# User_Interface.net
KiCad netlist of a schematic drawn in Altium Designer
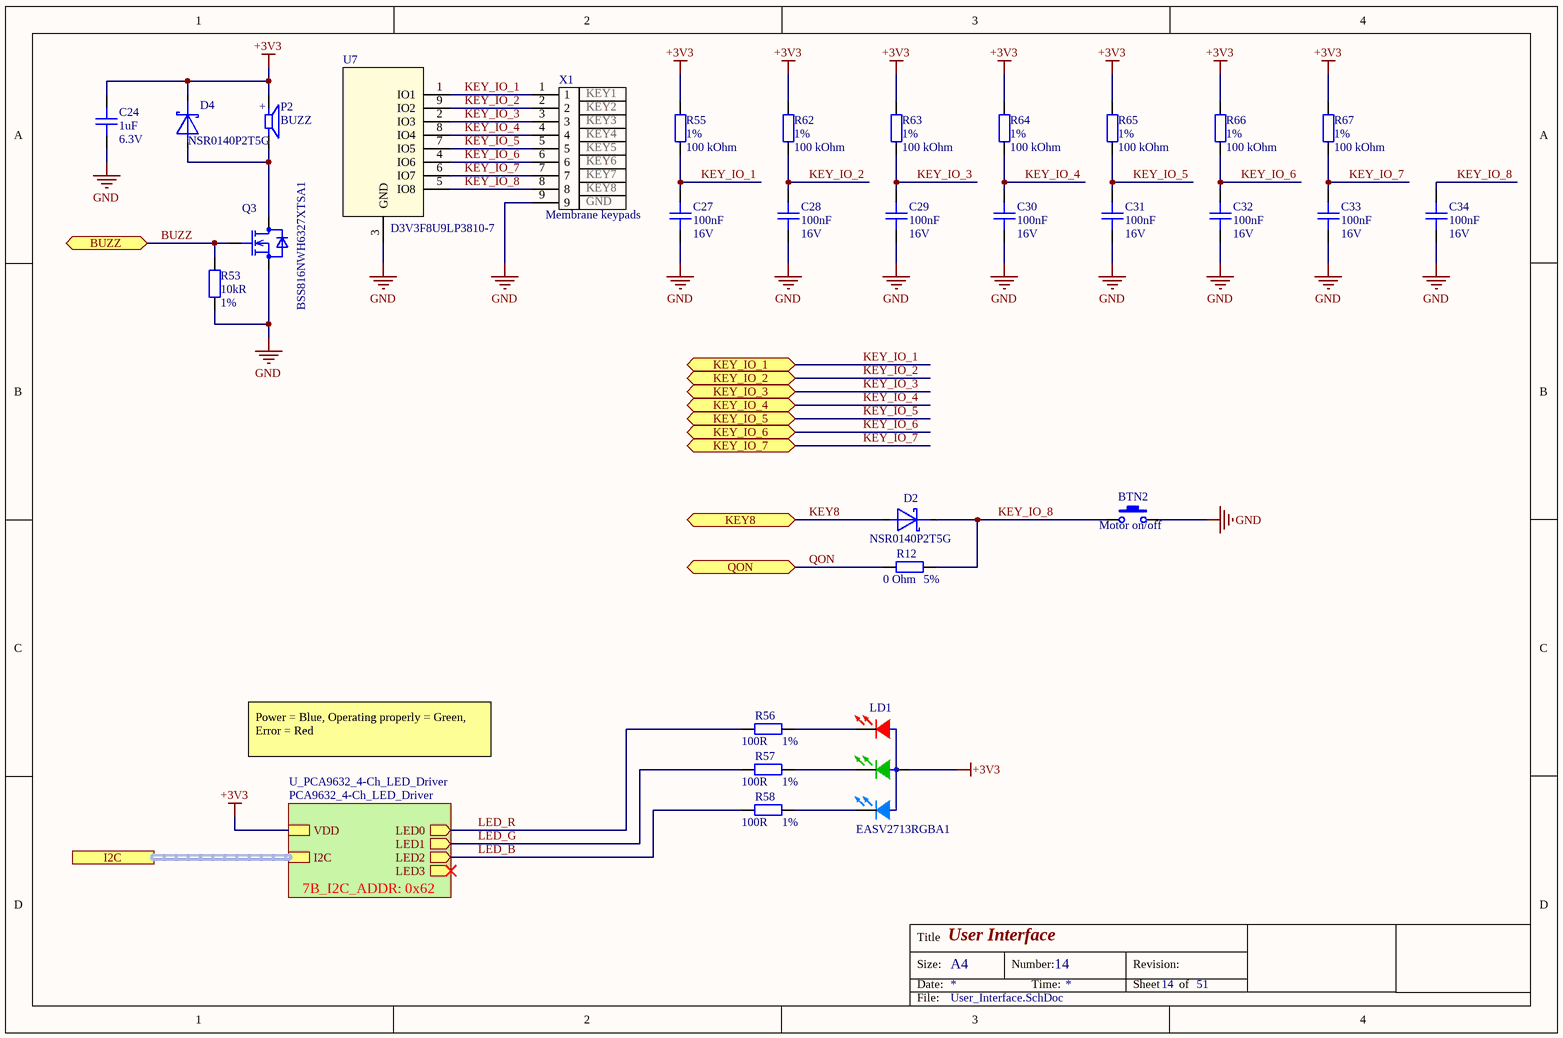
[diagram p0: User_Interface.SchDoc]

(export (version "E")
  (design (tool "Eeschema 10.0.6"))
  (components
    (comp (ref "BTN2")
      (value "Motor on/off")
      (footprint "SWITCH KMS231GLFS")
      (description "SWITCH TACTILE SPST-NO 0.05A 50V")
      (fields (field (name "MANUFACTURER") "C&K") (field (name "MANUFACTURER PART NUMBER") "KMS231GLFS"))
      (libsource (lib "Control_Board_Model") (part "SWITCH TACTILE SPST-NO 0.05A 50V"))
    )
    (comp (ref "C24")
      (value "CAP CER 1UF 6.3V X5R 0402")
      (footprint "C0402")
      (description "1µF ±10% 6.3V Ceramic Capacitor X5R 0402 (1005 Metric)")
      (fields
        (field (name "MANUFACTURER") "Yageo")
        (field (name "MANUFACTURER PART NUMBER") "CC0402KRX5R5BB105")
        (field (name "CAPACITANCE") "1uF")
        (field (name "VOLTAGE RATING") "6.3V")
      )
      (libsource (lib "capacitors_smd") (part "CAP CER 1UF 6.3V X5R 0402"))
    )
    (comp (ref "C27")
      (value "CAP CER 0.1UF 16V X7R 0402")
      (footprint "C0402")
      (description "0.1µF ±10% 16V Ceramic Capacitor X7R 0402 (1005 Metric)")
      (fields
        (field (name "MANUFACTURER PART NUMBER") "CC0402KRX7R7BB104")
        (field (name "MANUFACTURER") "Yageo")
        (field (name "CAPACITANCE") "100nF")
        (field (name "VOLTAGE") "16V")
      )
      (libsource (lib "capacitors_smd") (part "CAP CER 0.1UF 16V X7R 0402"))
    )
    (comp (ref "C28")
      (value "CAP CER 0.1UF 16V X7R 0402")
      (footprint "C0402")
      (description "0.1µF ±10% 16V Ceramic Capacitor X7R 0402 (1005 Metric)")
      (fields
        (field (name "MANUFACTURER PART NUMBER") "CC0402KRX7R7BB104")
        (field (name "MANUFACTURER") "Yageo")
        (field (name "CAPACITANCE") "100nF")
        (field (name "VOLTAGE") "16V")
      )
      (libsource (lib "capacitors_smd") (part "CAP CER 0.1UF 16V X7R 0402"))
    )
    (comp (ref "C29")
      (value "CAP CER 0.1UF 16V X7R 0402")
      (footprint "C0402")
      (description "0.1µF ±10% 16V Ceramic Capacitor X7R 0402 (1005 Metric)")
      (fields
        (field (name "MANUFACTURER PART NUMBER") "CC0402KRX7R7BB104")
        (field (name "MANUFACTURER") "Yageo")
        (field (name "CAPACITANCE") "100nF")
        (field (name "VOLTAGE") "16V")
      )
      (libsource (lib "capacitors_smd") (part "CAP CER 0.1UF 16V X7R 0402"))
    )
    (comp (ref "C30")
      (value "CAP CER 0.1UF 16V X7R 0402")
      (footprint "C0402")
      (description "0.1µF ±10% 16V Ceramic Capacitor X7R 0402 (1005 Metric)")
      (fields
        (field (name "MANUFACTURER PART NUMBER") "CC0402KRX7R7BB104")
        (field (name "MANUFACTURER") "Yageo")
        (field (name "CAPACITANCE") "100nF")
        (field (name "VOLTAGE") "16V")
      )
      (libsource (lib "capacitors_smd") (part "CAP CER 0.1UF 16V X7R 0402"))
    )
    (comp (ref "C31")
      (value "CAP CER 0.1UF 16V X7R 0402")
      (footprint "C0402")
      (description "0.1µF ±10% 16V Ceramic Capacitor X7R 0402 (1005 Metric)")
      (fields
        (field (name "MANUFACTURER PART NUMBER") "CC0402KRX7R7BB104")
        (field (name "MANUFACTURER") "Yageo")
        (field (name "CAPACITANCE") "100nF")
        (field (name "VOLTAGE") "16V")
      )
      (libsource (lib "capacitors_smd") (part "CAP CER 0.1UF 16V X7R 0402"))
    )
    (comp (ref "C32")
      (value "CAP CER 0.1UF 16V X7R 0402")
      (footprint "C0402")
      (description "0.1µF ±10% 16V Ceramic Capacitor X7R 0402 (1005 Metric)")
      (fields
        (field (name "MANUFACTURER PART NUMBER") "CC0402KRX7R7BB104")
        (field (name "MANUFACTURER") "Yageo")
        (field (name "CAPACITANCE") "100nF")
        (field (name "VOLTAGE") "16V")
      )
      (libsource (lib "capacitors_smd") (part "CAP CER 0.1UF 16V X7R 0402"))
    )
    (comp (ref "C33")
      (value "CAP CER 0.1UF 16V X7R 0402")
      (footprint "C0402")
      (description "0.1µF ±10% 16V Ceramic Capacitor X7R 0402 (1005 Metric)")
      (fields
        (field (name "MANUFACTURER PART NUMBER") "CC0402KRX7R7BB104")
        (field (name "MANUFACTURER") "Yageo")
        (field (name "CAPACITANCE") "100nF")
        (field (name "VOLTAGE") "16V")
      )
      (libsource (lib "capacitors_smd") (part "CAP CER 0.1UF 16V X7R 0402"))
    )
    (comp (ref "C34")
      (value "CAP CER 0.1UF 16V X7R 0402")
      (footprint "C0402")
      (description "0.1µF ±10% 16V Ceramic Capacitor X7R 0402 (1005 Metric)")
      (fields
        (field (name "MANUFACTURER PART NUMBER") "CC0402KRX7R7BB104")
        (field (name "MANUFACTURER") "Yageo")
        (field (name "CAPACITANCE") "100nF")
        (field (name "VOLTAGE") "16V")
      )
      (libsource (lib "capacitors_smd") (part "CAP CER 0.1UF 16V X7R 0402"))
    )
    (comp (ref "D2")
      (value "NSR0140P2T5G")
      (footprint "SODFL100X40-2N")
      (description "Diode Schottky 30V 70mA (DC) Surface Mount SOD-923")
      (fields (field (name "MANUFACTURER") "ON Semiconductor"))
      (libsource (lib "Control_Board_Model") (part "DIODE SCHOTTKY 30V 70MA SOD923"))
    )
    (comp (ref "D4")
      (value "NSR0140P2T5G")
      (footprint "SODFL100X40-2N")
      (description "Diode Schottky 30V 70mA (DC) Surface Mount SOD-923")
      (fields (field (name "MANUFACTURER") "ON Semiconductor"))
      (libsource (lib "diodes_schottky") (part "DIODE SCHOTTKY 30V 70MA SOD923"))
    )
    (comp (ref "LD1")
      (value "EASV2713RGBA1")
      (footprint "LED_EASV2713RGBA1")
      (fields (field (name "MANUFACTURER") "Everlight Electronics Co Ltd"))
      (libsource (lib "Control_Board_Model") (part "LED RGB PCB SIDE VIEW SMD"))
    )
    (comp (ref "P2")
      (value "BUZZ")
      (footprint "SMT-0440-S-R_PUI")
      (description "Buzzers Transducer, Externally Driven 90mA 4kHz 70dB @ 3V, 10cm Surface Mount Solder Pads")
      (fields
        (field (name "MANUFACTURER") "Projects Unlimited")
        (field (name "MANUFACTURER PART NUMBER") "SMT-0440-S-R")
      )
      (libsource (lib "BLDC_Motor_Driver") (part "AUDIO MAGNETIC XDCR 2-4V SMD"))
    )
    (comp (ref "Q3")
      (value "BSS816NWH6327XTSA1")
      (footprint "SOT-323")
      (description "N-Channel 20V 1.4A (Ta) 500mW (Ta) Surface Mount PG-SOT323-3")
      (fields (field (name "MANUFACTURER") "Infineon"))
      (libsource (lib "mosfets") (part "MOSFET BSS816NWH6327XTSA1 N-CH 20V 1.4A SOT323"))
    )
    (comp (ref "R12")
      (value "RES SMD 0 OHM JUMPER 1/16W 0402")
      (footprint "R0402")
      (description "0 Ohms Jumper 0.063W, 1/16W Chip Resistor 0402 (1005 Metric) Moisture Resistant Thick Film")
      (fields
        (field (name "MANUFACTURER") "Yageo")
        (field (name "MANUFACTURER PART NUMBER") "RC0402JR-070RL")
        (field (name "TOLERANCE") "5%")
        (field (name "RESISTANCE") "0 Ohm")
      )
      (libsource (lib "resistors_smd") (part "RES SMD 0 OHM JUMPER 1/16W 0402"))
    )
    (comp (ref "R53")
      (value "RES SMD 10K OHM 1% 1/16W 0402")
      (footprint "R0402")
      (description "10 kOhms ±1% 0.063W, 1/16W Chip Resistor 0402 (1005 Metric) Moisture Resistant Thick Film")
      (fields
        (field (name "MANUFACTURER PART NUMBER") "RC0402FR-0710KP")
        (field (name "MANUFACTURER") "Yageo")
        (field (name "RESISTANCE") "10kR")
        (field (name "TOLERANCE") "1%")
      )
      (libsource (lib "resistors_smd") (part "RES SMD 10K OHM 1% 1/16W 0402"))
    )
    (comp (ref "R55")
      (value "RES SMD 100K OHM 1% 1/16W 0402")
      (footprint "R0402")
      (description "100 kOhms ±1% 0.063W, 1/16W Chip Resistor 0402 (1005 Metric) Moisture Resistant Thick Film")
      (fields
        (field (name "MANUFACTURER") "Yageo")
        (field (name "MANUFACTURER PART NUMBER") "RC0402FR-07100KL")
        (field (name "TOLERANCE") "1%")
        (field (name "RESISTANCE") "100 kOhm")
      )
      (libsource (lib "Control_Board_Model") (part "RES SMD 100K OHM 1% 1/16W 0402"))
    )
    (comp (ref "R56")
      (value "RES SMD 100 OHM 1% 1/16W 0402")
      (footprint "R0402")
      (description "100 Ohms ±1% 0.063W, 1/16W Chip Resistor 0402 (1005 Metric) Moisture Resistant Thick Film")
      (fields
        (field (name "MANUFACTURER") "Yageo")
        (field (name "MANUFACTURER PART NUMBER") "RC0402FR-07100RL")
        (field (name "TOLERANCE") "1%")
        (field (name "RESISTANCE") "100R")
      )
      (libsource (lib "Control_Board_Model") (part "RES SMD 100 OHM 1% 1/16W 0402"))
    )
    (comp (ref "R57")
      (value "RES SMD 100 OHM 1% 1/16W 0402")
      (footprint "R0402")
      (description "100 Ohms ±1% 0.063W, 1/16W Chip Resistor 0402 (1005 Metric) Moisture Resistant Thick Film")
      (fields
        (field (name "MANUFACTURER") "Yageo")
        (field (name "MANUFACTURER PART NUMBER") "RC0402FR-07100RL")
        (field (name "TOLERANCE") "1%")
        (field (name "RESISTANCE") "100R")
      )
      (libsource (lib "Control_Board_Model") (part "RES SMD 100 OHM 1% 1/16W 0402"))
    )
    (comp (ref "R58")
      (value "RES SMD 100 OHM 1% 1/16W 0402")
      (footprint "R0402")
      (description "100 Ohms ±1% 0.063W, 1/16W Chip Resistor 0402 (1005 Metric) Moisture Resistant Thick Film")
      (fields
        (field (name "MANUFACTURER") "Yageo")
        (field (name "MANUFACTURER PART NUMBER") "RC0402FR-07100RL")
        (field (name "TOLERANCE") "1%")
        (field (name "RESISTANCE") "100R")
      )
      (libsource (lib "Control_Board_Model") (part "RES SMD 100 OHM 1% 1/16W 0402"))
    )
    (comp (ref "R62")
      (value "RES SMD 100K OHM 1% 1/16W 0402")
      (footprint "R0402")
      (description "100 kOhms ±1% 0.063W, 1/16W Chip Resistor 0402 (1005 Metric) Moisture Resistant Thick Film")
      (fields
        (field (name "MANUFACTURER") "Yageo")
        (field (name "MANUFACTURER PART NUMBER") "RC0402FR-07100KL")
        (field (name "TOLERANCE") "1%")
        (field (name "RESISTANCE") "100 kOhm")
      )
      (libsource (lib "Control_Board_Model") (part "RES SMD 100K OHM 1% 1/16W 0402"))
    )
    (comp (ref "R63")
      (value "RES SMD 100K OHM 1% 1/16W 0402")
      (footprint "R0402")
      (description "100 kOhms ±1% 0.063W, 1/16W Chip Resistor 0402 (1005 Metric) Moisture Resistant Thick Film")
      (fields
        (field (name "MANUFACTURER") "Yageo")
        (field (name "MANUFACTURER PART NUMBER") "RC0402FR-07100KL")
        (field (name "TOLERANCE") "1%")
        (field (name "RESISTANCE") "100 kOhm")
      )
      (libsource (lib "Control_Board_Model") (part "RES SMD 100K OHM 1% 1/16W 0402"))
    )
    (comp (ref "R64")
      (value "RES SMD 100K OHM 1% 1/16W 0402")
      (footprint "R0402")
      (description "100 kOhms ±1% 0.063W, 1/16W Chip Resistor 0402 (1005 Metric) Moisture Resistant Thick Film")
      (fields
        (field (name "MANUFACTURER") "Yageo")
        (field (name "MANUFACTURER PART NUMBER") "RC0402FR-07100KL")
        (field (name "TOLERANCE") "1%")
        (field (name "RESISTANCE") "100 kOhm")
      )
      (libsource (lib "Control_Board_Model") (part "RES SMD 100K OHM 1% 1/16W 0402"))
    )
    (comp (ref "R65")
      (value "RES SMD 100K OHM 1% 1/16W 0402")
      (footprint "R0402")
      (description "100 kOhms ±1% 0.063W, 1/16W Chip Resistor 0402 (1005 Metric) Moisture Resistant Thick Film")
      (fields
        (field (name "MANUFACTURER") "Yageo")
        (field (name "MANUFACTURER PART NUMBER") "RC0402FR-07100KL")
        (field (name "TOLERANCE") "1%")
        (field (name "RESISTANCE") "100 kOhm")
      )
      (libsource (lib "Control_Board_Model") (part "RES SMD 100K OHM 1% 1/16W 0402"))
    )
    (comp (ref "R66")
      (value "RES SMD 100K OHM 1% 1/16W 0402")
      (footprint "R0402")
      (description "100 kOhms ±1% 0.063W, 1/16W Chip Resistor 0402 (1005 Metric) Moisture Resistant Thick Film")
      (fields
        (field (name "MANUFACTURER") "Yageo")
        (field (name "MANUFACTURER PART NUMBER") "RC0402FR-07100KL")
        (field (name "TOLERANCE") "1%")
        (field (name "RESISTANCE") "100 kOhm")
      )
      (libsource (lib "Control_Board_Model") (part "RES SMD 100K OHM 1% 1/16W 0402"))
    )
    (comp (ref "R67")
      (value "RES SMD 100K OHM 1% 1/16W 0402")
      (footprint "R0402")
      (description "100 kOhms ±1% 0.063W, 1/16W Chip Resistor 0402 (1005 Metric) Moisture Resistant Thick Film")
      (fields
        (field (name "MANUFACTURER") "Yageo")
        (field (name "MANUFACTURER PART NUMBER") "RC0402FR-07100KL")
        (field (name "TOLERANCE") "1%")
        (field (name "RESISTANCE") "100 kOhm")
      )
      (libsource (lib "Control_Board_Model") (part "RES SMD 100K OHM 1% 1/16W 0402"))
    )
    (comp (ref "U7")
      (value "D3V3F8U9LP3810-7")
      (footprint "U-DFN3810-9")
      (description "5V (Typ) Clamp 5A (8/20µs) Ipp Tvs Diode Surface Mount U-DFN3810-9")
      (fields (field (name "MANUFACTURER") "Diodes"))
      (libsource (lib "Control_Board_Model") (part "TVS DIODE PP U-DFN3810-9"))
    )
    (comp (ref "X1")
      (value "Membrane keypads")
      (footprint "CONN_0525590952")
      (description "9 Position FFC, FPC Connector Contacts, Vertical - 1 Sided 0.020\" (0.50mm) Surface Mount")
      (fields
        (field (name "MANUFACTURER") "Molex")
        (field (name "MANUFACTURER PART NUMBER") "0525590952")
        (field (name "PIN_1") "KEY1")
        (field (name "PIN_2") "KEY2")
        (field (name "PIN_3") "KEY3")
        (field (name "PIN_4") "KEY4")
        (field (name "PIN_5") "KEY5")
        (field (name "PIN_6") "KEY6")
        (field (name "PIN_7") "KEY7")
        (field (name "PIN_8") "KEY8")
        (field (name "PIN_9") "GND")
      )
      (libsource (lib "Control_Board_Model") (part "CONN FFC VERT 9POS 0.50MM SMD"))
    )
  )
  (nets
    (net (code "2") (name "+3V3") (class "Default")
      (node (ref "C24") (pin "1") (pinfunction "1_1") (pintype "passive"))
      (node (ref "D4") (pin "1") (pinfunction "K_1") (pintype "passive"))
      (node (ref "LD1") (pin "1") (pinfunction "A_1") (pintype "passive"))
      (node (ref "P2") (pin "1") (pinfunction "1_1") (pintype "passive"))
      (node (ref "R55") (pin "2") (pinfunction "2_2") (pintype "passive"))
      (node (ref "R62") (pin "2") (pinfunction "2_2") (pintype "passive"))
      (node (ref "R63") (pin "2") (pinfunction "2_2") (pintype "passive"))
      (node (ref "R64") (pin "2") (pinfunction "2_2") (pintype "passive"))
      (node (ref "R65") (pin "2") (pinfunction "2_2") (pintype "passive"))
      (node (ref "R66") (pin "2") (pinfunction "2_2") (pintype "passive"))
      (node (ref "R67") (pin "2") (pinfunction "2_2") (pintype "passive"))
    )
    (net (code "3") (name "/BUZZ") (class "Default")
      (node (ref "Q3") (pin "1") (pinfunction "G_1") (pintype "passive"))
      (node (ref "R53") (pin "1") (pinfunction "1_1") (pintype "passive"))
    )
    (net (code "5") (name "/KEY8") (class "Default")
      (node (ref "D2") (pin "2") (pinfunction "A_2") (pintype "passive"))
    )
    (net (code "6") (name "/KEY_IO_1") (class "Default")
      (node (ref "C27") (pin "1") (pinfunction "1_1") (pintype "passive"))
      (node (ref "R55") (pin "1") (pinfunction "1_1") (pintype "passive"))
      (node (ref "U7") (pin "1") (pinfunction "IO1_1") (pintype "passive"))
      (node (ref "X1") (pin "1") (pinfunction "1_1") (pintype "passive"))
    )
    (net (code "7") (name "/KEY_IO_2") (class "Default")
      (node (ref "C28") (pin "1") (pinfunction "1_1") (pintype "passive"))
      (node (ref "R62") (pin "1") (pinfunction "1_1") (pintype "passive"))
      (node (ref "U7") (pin "9") (pinfunction "IO2_9") (pintype "passive"))
      (node (ref "X1") (pin "2") (pinfunction "2_2") (pintype "passive"))
    )
    (net (code "8") (name "/KEY_IO_3") (class "Default")
      (node (ref "C29") (pin "1") (pinfunction "1_1") (pintype "passive"))
      (node (ref "R63") (pin "1") (pinfunction "1_1") (pintype "passive"))
      (node (ref "U7") (pin "2") (pinfunction "IO3_2") (pintype "passive"))
      (node (ref "X1") (pin "3") (pinfunction "3_3") (pintype "passive"))
    )
    (net (code "9") (name "/KEY_IO_4") (class "Default")
      (node (ref "C30") (pin "1") (pinfunction "1_1") (pintype "passive"))
      (node (ref "R64") (pin "1") (pinfunction "1_1") (pintype "passive"))
      (node (ref "U7") (pin "8") (pinfunction "IO4_8") (pintype "passive"))
      (node (ref "X1") (pin "4") (pinfunction "4_4") (pintype "passive"))
    )
    (net (code "10") (name "/KEY_IO_5") (class "Default")
      (node (ref "C31") (pin "1") (pinfunction "1_1") (pintype "passive"))
      (node (ref "R65") (pin "1") (pinfunction "1_1") (pintype "passive"))
      (node (ref "U7") (pin "7") (pinfunction "IO5_7") (pintype "passive"))
      (node (ref "X1") (pin "5") (pinfunction "5_5") (pintype "passive"))
    )
    (net (code "11") (name "/KEY_IO_6") (class "Default")
      (node (ref "C32") (pin "1") (pinfunction "1_1") (pintype "passive"))
      (node (ref "R66") (pin "1") (pinfunction "1_1") (pintype "passive"))
      (node (ref "U7") (pin "4") (pinfunction "IO6_4") (pintype "passive"))
      (node (ref "X1") (pin "6") (pinfunction "6_6") (pintype "passive"))
    )
    (net (code "12") (name "/KEY_IO_7") (class "Default")
      (node (ref "C33") (pin "1") (pinfunction "1_1") (pintype "passive"))
      (node (ref "R67") (pin "1") (pinfunction "1_1") (pintype "passive"))
      (node (ref "U7") (pin "6") (pinfunction "IO7_6") (pintype "passive"))
      (node (ref "X1") (pin "7") (pinfunction "7_7") (pintype "passive"))
    )
    (net (code "13") (name "/KEY_IO_8") (class "Default")
      (node (ref "BTN2") (pin "1") (pinfunction "1_1") (pintype "passive"))
      (node (ref "C34") (pin "1") (pinfunction "1_1") (pintype "passive"))
      (node (ref "D2") (pin "1") (pinfunction "K_1") (pintype "passive"))
      (node (ref "R12") (pin "1") (pinfunction "1_1") (pintype "passive"))
      (node (ref "U7") (pin "5") (pinfunction "IO8_5") (pintype "passive"))
      (node (ref "X1") (pin "8") (pinfunction "8_8") (pintype "passive"))
    )
    (net (code "15") (name "/LED_B") (class "Default")
      (node (ref "R58") (pin "2") (pinfunction "2_2") (pintype "passive"))
    )
    (net (code "16") (name "/LED_G") (class "Default")
      (node (ref "R57") (pin "2") (pinfunction "2_2") (pintype "passive"))
    )
    (net (code "17") (name "/LED_R") (class "Default")
      (node (ref "R56") (pin "2") (pinfunction "2_2") (pintype "passive"))
    )
    (net (code "18") (name "/QON") (class "Default")
      (node (ref "R12") (pin "2") (pinfunction "2_2") (pintype "passive"))
    )
    (net (code "19") (name "GND") (class "Default")
      (node (ref "BTN2") (pin "2") (pinfunction "2_2") (pintype "passive"))
      (node (ref "C24") (pin "2") (pinfunction "2_2") (pintype "passive"))
      (node (ref "C27") (pin "2") (pinfunction "2_2") (pintype "passive"))
      (node (ref "C28") (pin "2") (pinfunction "2_2") (pintype "passive"))
      (node (ref "C29") (pin "2") (pinfunction "2_2") (pintype "passive"))
      (node (ref "C30") (pin "2") (pinfunction "2_2") (pintype "passive"))
      (node (ref "C31") (pin "2") (pinfunction "2_2") (pintype "passive"))
      (node (ref "C32") (pin "2") (pinfunction "2_2") (pintype "passive"))
      (node (ref "C33") (pin "2") (pinfunction "2_2") (pintype "passive"))
      (node (ref "C34") (pin "2") (pinfunction "2_2") (pintype "passive"))
      (node (ref "Q3") (pin "2") (pinfunction "S_2") (pintype "passive"))
      (node (ref "R53") (pin "2") (pinfunction "2_2") (pintype "passive"))
      (node (ref "U7") (pin "3") (pinfunction "GND_3") (pintype "power_in"))
      (node (ref "X1") (pin "9") (pinfunction "9_9") (pintype "passive"))
    )
    (net (code "20") (name "Net-(D4-A)") (class "Default")
      (node (ref "D4") (pin "2") (pinfunction "A_2") (pintype "passive"))
      (node (ref "P2") (pin "2") (pinfunction "2_2") (pintype "passive"))
      (node (ref "Q3") (pin "3") (pinfunction "D_3") (pintype "passive"))
    )
    (net (code "21") (name "Net-(LD1-BK)") (class "Default")
      (node (ref "LD1") (pin "4") (pinfunction "BK_4") (pintype "passive"))
      (node (ref "R58") (pin "1") (pinfunction "1_1") (pintype "passive"))
    )
    (net (code "22") (name "Net-(LD1-GK)") (class "Default")
      (node (ref "LD1") (pin "2") (pinfunction "GK_2") (pintype "passive"))
      (node (ref "R57") (pin "1") (pinfunction "1_1") (pintype "passive"))
    )
    (net (code "23") (name "Net-(LD1-RK)") (class "Default")
      (node (ref "LD1") (pin "3") (pinfunction "RK_3") (pintype "passive"))
      (node (ref "R56") (pin "1") (pinfunction "1_1") (pintype "passive"))
    )
  )
)
